# Arduino_NANO_DRAM_Tester.net
KiCad netlist of a schematic drawn in EAGLE
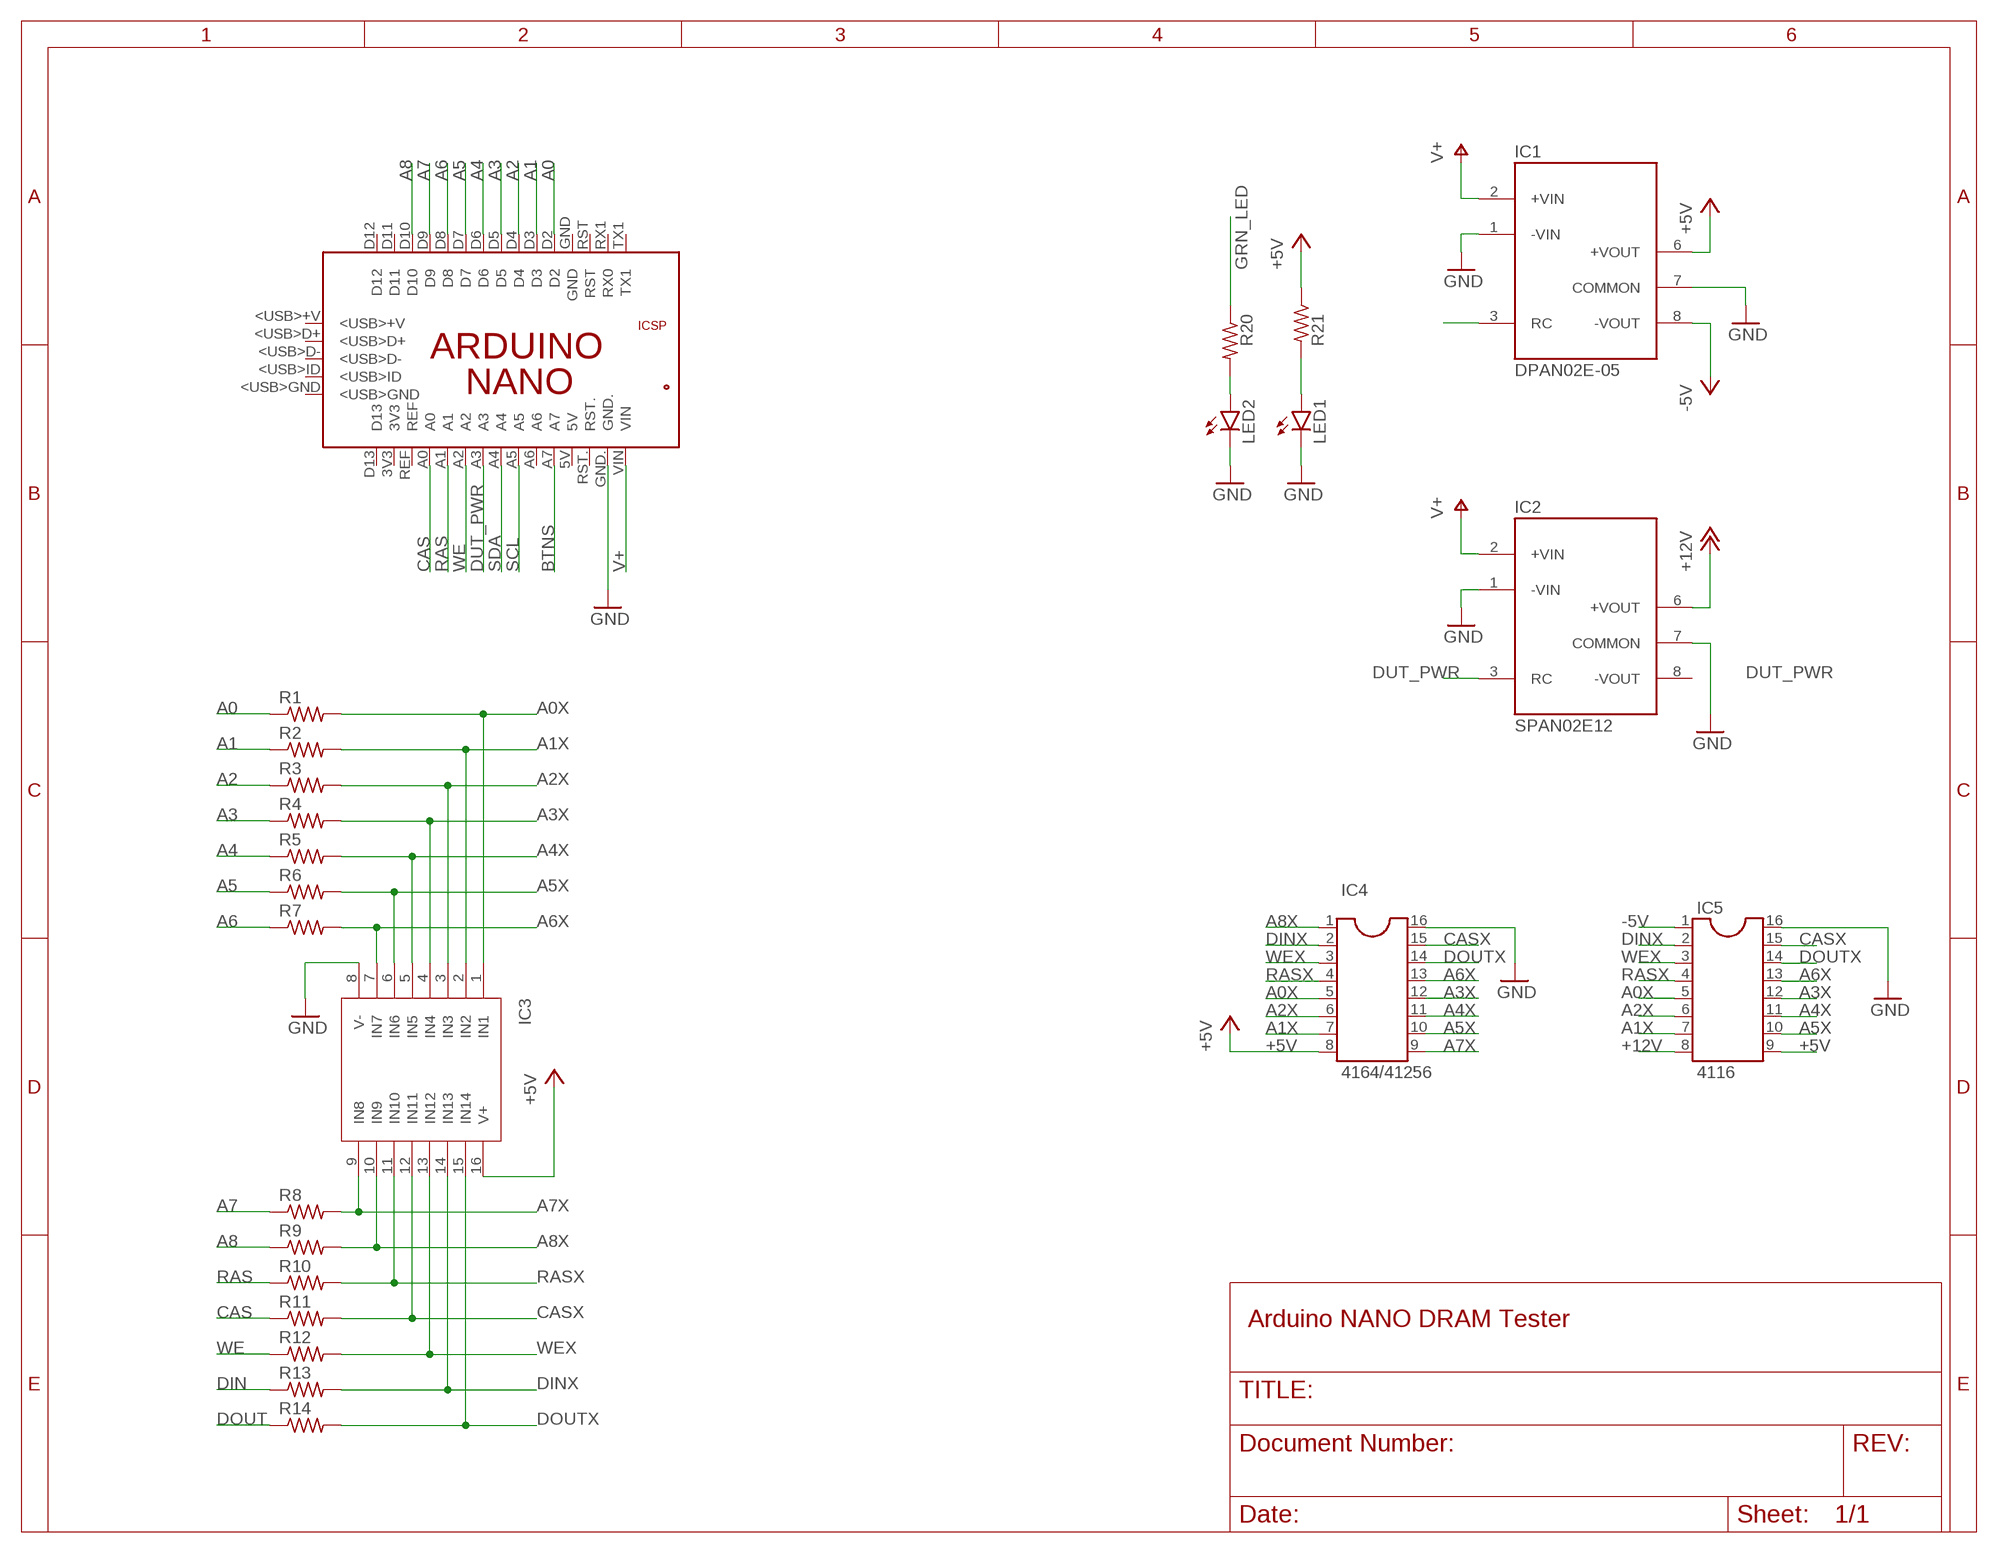
[diagram p0: schematic, sheet 1]

(export (version "E")
  (design (tool "Eeschema 10.0.6"))
  (components
    (comp (ref "IC1")
      (value "DPAN02E-05")
      (footprint "eagle-import:SIP7")
      (libsource (lib "eagle-import") (part "DPAN02"))
    )
    (comp (ref "IC2")
      (value "SPAN02E12")
      (footprint "eagle-import:SIP7")
      (libsource (lib "eagle-import") (part "DPAN02"))
    )
    (comp (ref "IC3")
      (value "SP720")
      (footprint "eagle-import:DIL16")
      (libsource (lib "eagle-import") (part "SP720"))
    )
    (comp (ref "IC4")
      (value "4164/41256")
      (footprint "eagle-import:DIL16")
      (libsource (lib "eagle-import") (part "DIL16"))
    )
    (comp (ref "IC5")
      (value "4116")
      (footprint "eagle-import:SOCKET-16")
      (libsource (lib "eagle-import") (part "DIL16S"))
    )
    (comp (ref "LED1")
      (value "LED5MM")
      (footprint "eagle-import:LED5MM")
      (libsource (lib "eagle-import") (part "LED5MM"))
    )
    (comp (ref "LED2")
      (value "LED5MM")
      (footprint "eagle-import:LED5MM")
      (libsource (lib "eagle-import") (part "LED5MM"))
    )
    (comp (ref "PCB1")
      (value "ARDUINO_NANO")
      (footprint "eagle-import:ARDUINO_NANO")
      (libsource (lib "eagle-import") (part "ARDUINO_NANO"))
    )
    (comp (ref "R1")
      (value "R-US_V235/17")
      (footprint "eagle-import:V235_17")
      (libsource (lib "eagle-import") (part "R-US_V235/17"))
    )
    (comp (ref "R2")
      (value "R-US_V235/17")
      (footprint "eagle-import:V235_17")
      (libsource (lib "eagle-import") (part "R-US_V235/17"))
    )
    (comp (ref "R3")
      (value "R-US_V235/17")
      (footprint "eagle-import:V235_17")
      (libsource (lib "eagle-import") (part "R-US_V235/17"))
    )
    (comp (ref "R4")
      (value "R-US_V235/17")
      (footprint "eagle-import:V235_17")
      (libsource (lib "eagle-import") (part "R-US_V235/17"))
    )
    (comp (ref "R5")
      (value "R-US_V235/17")
      (footprint "eagle-import:V235_17")
      (libsource (lib "eagle-import") (part "R-US_V235/17"))
    )
    (comp (ref "R6")
      (value "R-US_V235/17")
      (footprint "eagle-import:V235_17")
      (libsource (lib "eagle-import") (part "R-US_V235/17"))
    )
    (comp (ref "R7")
      (value "R-US_V235/17")
      (footprint "eagle-import:V235_17")
      (libsource (lib "eagle-import") (part "R-US_V235/17"))
    )
    (comp (ref "R8")
      (value "R-US_V235/17")
      (footprint "eagle-import:V235_17")
      (libsource (lib "eagle-import") (part "R-US_V235/17"))
    )
    (comp (ref "R9")
      (value "R-US_V235/17")
      (footprint "eagle-import:V235_17")
      (libsource (lib "eagle-import") (part "R-US_V235/17"))
    )
    (comp (ref "R10")
      (value "R-US_V235/17")
      (footprint "eagle-import:V235_17")
      (libsource (lib "eagle-import") (part "R-US_V235/17"))
    )
    (comp (ref "R11")
      (value "R-US_V235/17")
      (footprint "eagle-import:V235_17")
      (libsource (lib "eagle-import") (part "R-US_V235/17"))
    )
    (comp (ref "R12")
      (value "R-US_V235/17")
      (footprint "eagle-import:V235_17")
      (libsource (lib "eagle-import") (part "R-US_V235/17"))
    )
    (comp (ref "R13")
      (value "R-US_V235/17")
      (footprint "eagle-import:V235_17")
      (libsource (lib "eagle-import") (part "R-US_V235/17"))
    )
    (comp (ref "R14")
      (value "R-US_V235/17")
      (footprint "eagle-import:V235_17")
      (libsource (lib "eagle-import") (part "R-US_V235/17"))
    )
    (comp (ref "R20")
      (value "R-US_0309/10")
      (footprint "eagle-import:0309_10")
      (libsource (lib "eagle-import") (part "resistor_348_R-US_0309/10"))
    )
    (comp (ref "R21")
      (value "R-US_0309/10")
      (footprint "eagle-import:0309_10")
      (libsource (lib "eagle-import") (part "resistor_348_R-US_0309/10"))
    )
  )
  (nets
    (net (code "1") (name "+5V") (class "Default")
      (node (ref "IC1") (pin "6") (pinfunction "+VOUT_6") (pintype "passive"))
      (node (ref "IC3") (pin "16") (pinfunction "V+_16") (pintype "input"))
      (node (ref "IC4") (pin "8") (pinfunction "8_8") (pintype "passive"))
      (node (ref "IC5") (pin "9") (pinfunction "9_9") (pintype "passive"))
      (node (ref "R21") (pin "1") (pinfunction "1_1") (pintype "passive"))
    )
    (net (code "2") (name "+12V") (class "Default")
      (node (ref "IC2") (pin "6") (pinfunction "+VOUT_6") (pintype "passive"))
      (node (ref "IC5") (pin "8") (pinfunction "8_8") (pintype "passive"))
    )
    (net (code "3") (name "-5V") (class "Default")
      (node (ref "IC1") (pin "8") (pinfunction "-VOUT_8") (pintype "passive"))
      (node (ref "IC5") (pin "1") (pinfunction "1_1") (pintype "passive"))
    )
    (net (code "4") (name "/A0") (class "Default")
      (node (ref "PCB1") (pin "D2") (pinfunction "D2_D2") (pintype "bidirectional"))
      (node (ref "R1") (pin "1") (pinfunction "1_1") (pintype "passive"))
    )
    (net (code "5") (name "/A0X") (class "Default")
      (node (ref "IC3") (pin "1") (pinfunction "IN1_1") (pintype "input"))
      (node (ref "IC4") (pin "5") (pinfunction "5_5") (pintype "passive"))
      (node (ref "IC5") (pin "5") (pinfunction "5_5") (pintype "passive"))
      (node (ref "R1") (pin "2") (pinfunction "2_2") (pintype "passive"))
    )
    (net (code "6") (name "/A1") (class "Default")
      (node (ref "PCB1") (pin "D3") (pinfunction "D3_D3") (pintype "bidirectional"))
      (node (ref "R2") (pin "1") (pinfunction "1_1") (pintype "passive"))
    )
    (net (code "7") (name "/A1X") (class "Default")
      (node (ref "IC3") (pin "2") (pinfunction "IN2_2") (pintype "input"))
      (node (ref "IC4") (pin "7") (pinfunction "7_7") (pintype "passive"))
      (node (ref "IC5") (pin "7") (pinfunction "7_7") (pintype "passive"))
      (node (ref "R2") (pin "2") (pinfunction "2_2") (pintype "passive"))
    )
    (net (code "8") (name "/A2") (class "Default")
      (node (ref "PCB1") (pin "D4") (pinfunction "D4_D4") (pintype "bidirectional"))
      (node (ref "R3") (pin "1") (pinfunction "1_1") (pintype "passive"))
    )
    (net (code "9") (name "/A2X") (class "Default")
      (node (ref "IC3") (pin "3") (pinfunction "IN3_3") (pintype "input"))
      (node (ref "IC4") (pin "6") (pinfunction "6_6") (pintype "passive"))
      (node (ref "IC5") (pin "6") (pinfunction "6_6") (pintype "passive"))
      (node (ref "R3") (pin "2") (pinfunction "2_2") (pintype "passive"))
    )
    (net (code "10") (name "/A3") (class "Default")
      (node (ref "PCB1") (pin "D5") (pinfunction "D5_D5") (pintype "bidirectional"))
      (node (ref "R4") (pin "1") (pinfunction "1_1") (pintype "passive"))
    )
    (net (code "11") (name "/A3X") (class "Default")
      (node (ref "IC3") (pin "4") (pinfunction "IN4_4") (pintype "input"))
      (node (ref "IC4") (pin "12") (pinfunction "12_12") (pintype "passive"))
      (node (ref "IC5") (pin "12") (pinfunction "12_12") (pintype "passive"))
      (node (ref "R4") (pin "2") (pinfunction "2_2") (pintype "passive"))
    )
    (net (code "12") (name "/A4") (class "Default")
      (node (ref "PCB1") (pin "D6") (pinfunction "D6_D6") (pintype "bidirectional"))
      (node (ref "R5") (pin "1") (pinfunction "1_1") (pintype "passive"))
    )
    (net (code "13") (name "/A4X") (class "Default")
      (node (ref "IC3") (pin "5") (pinfunction "IN5_5") (pintype "input"))
      (node (ref "IC4") (pin "11") (pinfunction "11_11") (pintype "passive"))
      (node (ref "IC5") (pin "11") (pinfunction "11_11") (pintype "passive"))
      (node (ref "R5") (pin "2") (pinfunction "2_2") (pintype "passive"))
    )
    (net (code "14") (name "/A5") (class "Default")
      (node (ref "PCB1") (pin "D7") (pinfunction "D7_D7") (pintype "bidirectional"))
      (node (ref "R6") (pin "1") (pinfunction "1_1") (pintype "passive"))
    )
    (net (code "15") (name "/A5X") (class "Default")
      (node (ref "IC3") (pin "6") (pinfunction "IN6_6") (pintype "input"))
      (node (ref "IC4") (pin "10") (pinfunction "10_10") (pintype "passive"))
      (node (ref "IC5") (pin "10") (pinfunction "10_10") (pintype "passive"))
      (node (ref "R6") (pin "2") (pinfunction "2_2") (pintype "passive"))
    )
    (net (code "16") (name "/A6") (class "Default")
      (node (ref "PCB1") (pin "D8") (pinfunction "D8_D8") (pintype "bidirectional"))
      (node (ref "R7") (pin "1") (pinfunction "1_1") (pintype "passive"))
    )
    (net (code "17") (name "/A6X") (class "Default")
      (node (ref "IC3") (pin "7") (pinfunction "IN7_7") (pintype "input"))
      (node (ref "IC4") (pin "13") (pinfunction "13_13") (pintype "passive"))
      (node (ref "IC5") (pin "13") (pinfunction "13_13") (pintype "passive"))
      (node (ref "R7") (pin "2") (pinfunction "2_2") (pintype "passive"))
    )
    (net (code "18") (name "/A7") (class "Default")
      (node (ref "PCB1") (pin "D9") (pinfunction "D9_D9") (pintype "bidirectional"))
      (node (ref "R8") (pin "1") (pinfunction "1_1") (pintype "passive"))
    )
    (net (code "19") (name "/A7X") (class "Default")
      (node (ref "IC3") (pin "9") (pinfunction "IN8_9") (pintype "input"))
      (node (ref "IC4") (pin "9") (pinfunction "9_9") (pintype "passive"))
      (node (ref "R8") (pin "2") (pinfunction "2_2") (pintype "passive"))
    )
    (net (code "20") (name "/A8") (class "Default")
      (node (ref "PCB1") (pin "D10") (pinfunction "D10_D10") (pintype "bidirectional"))
      (node (ref "R9") (pin "1") (pinfunction "1_1") (pintype "passive"))
    )
    (net (code "21") (name "/A8X") (class "Default")
      (node (ref "IC3") (pin "10") (pinfunction "IN9_10") (pintype "input"))
      (node (ref "IC4") (pin "1") (pinfunction "1_1") (pintype "passive"))
      (node (ref "R9") (pin "2") (pinfunction "2_2") (pintype "passive"))
    )
    (net (code "22") (name "/BTNS") (class "Default")
      (node (ref "PCB1") (pin "A7") (pinfunction "A7_A7") (pintype "bidirectional"))
    )
    (net (code "23") (name "/CAS") (class "Default")
      (node (ref "PCB1") (pin "A0") (pinfunction "A0_A0") (pintype "bidirectional"))
      (node (ref "R11") (pin "1") (pinfunction "1_1") (pintype "passive"))
    )
    (net (code "24") (name "/CASX") (class "Default")
      (node (ref "IC3") (pin "12") (pinfunction "IN11_12") (pintype "input"))
      (node (ref "IC4") (pin "15") (pinfunction "15_15") (pintype "passive"))
      (node (ref "IC5") (pin "15") (pinfunction "15_15") (pintype "passive"))
      (node (ref "R11") (pin "2") (pinfunction "2_2") (pintype "passive"))
    )
    (net (code "25") (name "/DIN") (class "Default")
      (node (ref "R13") (pin "1") (pinfunction "1_1") (pintype "passive"))
    )
    (net (code "26") (name "/DINX") (class "Default")
      (node (ref "IC3") (pin "14") (pinfunction "IN13_14") (pintype "input"))
      (node (ref "IC4") (pin "2") (pinfunction "2_2") (pintype "passive"))
      (node (ref "IC5") (pin "2") (pinfunction "2_2") (pintype "passive"))
      (node (ref "R13") (pin "2") (pinfunction "2_2") (pintype "passive"))
    )
    (net (code "27") (name "/DOUT") (class "Default")
      (node (ref "R14") (pin "1") (pinfunction "1_1") (pintype "passive"))
    )
    (net (code "28") (name "/DOUTX") (class "Default")
      (node (ref "IC3") (pin "15") (pinfunction "IN14_15") (pintype "input"))
      (node (ref "IC4") (pin "14") (pinfunction "14_14") (pintype "passive"))
      (node (ref "IC5") (pin "14") (pinfunction "14_14") (pintype "passive"))
      (node (ref "R14") (pin "2") (pinfunction "2_2") (pintype "passive"))
    )
    (net (code "29") (name "/DUT_PWR") (class "Default")
      (node (ref "IC1") (pin "3") (pinfunction "RC_3") (pintype "input"))
      (node (ref "IC2") (pin "3") (pinfunction "RC_3") (pintype "input"))
      (node (ref "PCB1") (pin "A3") (pinfunction "A3_A3") (pintype "bidirectional"))
    )
    (net (code "30") (name "/GRN_LED") (class "Default")
      (node (ref "R20") (pin "1") (pinfunction "1_1") (pintype "passive"))
    )
    (net (code "31") (name "/RAS") (class "Default")
      (node (ref "PCB1") (pin "A1") (pinfunction "A1_A1") (pintype "bidirectional"))
      (node (ref "R10") (pin "1") (pinfunction "1_1") (pintype "passive"))
    )
    (net (code "32") (name "/RASX") (class "Default")
      (node (ref "IC3") (pin "11") (pinfunction "IN10_11") (pintype "input"))
      (node (ref "IC4") (pin "4") (pinfunction "4_4") (pintype "passive"))
      (node (ref "IC5") (pin "4") (pinfunction "4_4") (pintype "passive"))
      (node (ref "R10") (pin "2") (pinfunction "2_2") (pintype "passive"))
    )
    (net (code "33") (name "/SCL") (class "Default")
      (node (ref "PCB1") (pin "A5") (pinfunction "A5_A5") (pintype "bidirectional"))
    )
    (net (code "34") (name "/SDA") (class "Default")
      (node (ref "PCB1") (pin "A4") (pinfunction "A4_A4") (pintype "bidirectional"))
    )
    (net (code "35") (name "/WE") (class "Default")
      (node (ref "PCB1") (pin "A2") (pinfunction "A2_A2") (pintype "bidirectional"))
      (node (ref "R12") (pin "1") (pinfunction "1_1") (pintype "passive"))
    )
    (net (code "36") (name "/WEX") (class "Default")
      (node (ref "IC3") (pin "13") (pinfunction "IN12_13") (pintype "input"))
      (node (ref "IC4") (pin "3") (pinfunction "3_3") (pintype "passive"))
      (node (ref "IC5") (pin "3") (pinfunction "3_3") (pintype "passive"))
      (node (ref "R12") (pin "2") (pinfunction "2_2") (pintype "passive"))
    )
    (net (code "37") (name "GND") (class "Default")
      (node (ref "IC1") (pin "1") (pinfunction "-VIN_1") (pintype "input"))
      (node (ref "IC1") (pin "7") (pinfunction "COMMON_7") (pintype "passive"))
      (node (ref "IC2") (pin "1") (pinfunction "-VIN_1") (pintype "input"))
      (node (ref "IC2") (pin "7") (pinfunction "COMMON_7") (pintype "passive"))
      (node (ref "IC3") (pin "8") (pinfunction "V-_8") (pintype "input"))
      (node (ref "IC4") (pin "16") (pinfunction "16_16") (pintype "passive"))
      (node (ref "IC5") (pin "16") (pinfunction "16_16") (pintype "passive"))
      (node (ref "LED1") (pin "K") (pinfunction "C_K") (pintype "passive"))
      (node (ref "LED2") (pin "K") (pinfunction "C_K") (pintype "passive"))
      (node (ref "PCB1") (pin "GND.") (pinfunction "GND._GND.") (pintype "bidirectional"))
    )
    (net (code "38") (name "Net-(LED1-PadA)") (class "Default")
      (node (ref "LED1") (pin "A") (pinfunction "A_A") (pintype "passive"))
      (node (ref "R21") (pin "2") (pinfunction "2_2") (pintype "passive"))
    )
    (net (code "39") (name "Net-(LED2-PadA)") (class "Default")
      (node (ref "LED2") (pin "A") (pinfunction "A_A") (pintype "passive"))
      (node (ref "R20") (pin "2") (pinfunction "2_2") (pintype "passive"))
    )
    (net (code "40") (name "V+") (class "Default")
      (node (ref "IC1") (pin "2") (pinfunction "+VIN_2") (pintype "input"))
      (node (ref "IC2") (pin "2") (pinfunction "+VIN_2") (pintype "input"))
      (node (ref "PCB1") (pin "VIN") (pinfunction "VIN_VIN") (pintype "bidirectional"))
    )
    (net (code "41") (name "unconnected-(IC2--VOUT-Pad8)") (class "Default")
      (node (ref "IC2") (pin "8") (pinfunction "-VOUT_8") (pintype "passive"))
    )
    (net (code "42") (name "unconnected-(PCB1-Pad3V3)") (class "Default")
      (node (ref "PCB1") (pin "3V3") (pinfunction "3V3_3V3") (pintype "bidirectional"))
    )
    (net (code "43") (name "unconnected-(PCB1-Pad5V)") (class "Default")
      (node (ref "PCB1") (pin "5V") (pinfunction "5V_5V") (pintype "bidirectional"))
    )
    (net (code "44") (name "unconnected-(PCB1-Pad5V.)") (class "Default")
      (node (ref "PCB1") (pin "5V.") (pinfunction "5V._5V.") (pintype "bidirectional"))
    )
    (net (code "45") (name "unconnected-(PCB1-Pad<USB>+V)") (class "Default")
      (node (ref "PCB1") (pin "<USB>+V") (pinfunction "<USB>+V_<USB>+V") (pintype "bidirectional"))
    )
    (net (code "46") (name "unconnected-(PCB1-Pad<USB>D+)") (class "Default")
      (node (ref "PCB1") (pin "<USB>D+") (pinfunction "<USB>D+_<USB>D+") (pintype "bidirectional"))
    )
    (net (code "47") (name "unconnected-(PCB1-Pad<USB>D-)") (class "Default")
      (node (ref "PCB1") (pin "<USB>D-") (pinfunction "<USB>D-_<USB>D-") (pintype "bidirectional"))
    )
    (net (code "48") (name "unconnected-(PCB1-Pad<USB>GND)") (class "Default")
      (node (ref "PCB1") (pin "<USB>GND") (pinfunction "<USB>GND_<USB>GND") (pintype "bidirectional"))
    )
    (net (code "49") (name "unconnected-(PCB1-Pad<USB>ID)") (class "Default")
      (node (ref "PCB1") (pin "<USB>ID") (pinfunction "<USB>ID_<USB>ID") (pintype "bidirectional"))
    )
    (net (code "50") (name "unconnected-(PCB1-PadA6)") (class "Default")
      (node (ref "PCB1") (pin "A6") (pinfunction "A6_A6") (pintype "bidirectional"))
    )
    (net (code "51") (name "unconnected-(PCB1-PadD11)") (class "Default")
      (node (ref "PCB1") (pin "D11") (pinfunction "D11_D11") (pintype "bidirectional"))
    )
    (net (code "52") (name "unconnected-(PCB1-PadD12)") (class "Default")
      (node (ref "PCB1") (pin "D12") (pinfunction "D12_D12") (pintype "bidirectional"))
    )
    (net (code "53") (name "unconnected-(PCB1-PadD13)") (class "Default")
      (node (ref "PCB1") (pin "D13") (pinfunction "D13_D13") (pintype "bidirectional"))
    )
    (net (code "54") (name "unconnected-(PCB1-PadGND)") (class "Default")
      (node (ref "PCB1") (pin "GND") (pinfunction "GND_GND") (pintype "bidirectional"))
    )
    (net (code "55") (name "unconnected-(PCB1-PadGND_)") (class "Default")
      (node (ref "PCB1") (pin "GND_") (pinfunction "GND__GND_") (pintype "bidirectional"))
    )
    (net (code "56") (name "unconnected-(PCB1-PadMISO)") (class "Default")
      (node (ref "PCB1") (pin "MISO") (pinfunction "MISO_MISO") (pintype "bidirectional"))
    )
    (net (code "57") (name "unconnected-(PCB1-PadMOSI)") (class "Default")
      (node (ref "PCB1") (pin "MOSI") (pinfunction "MOSI_MOSI") (pintype "bidirectional"))
    )
    (net (code "58") (name "unconnected-(PCB1-PadREF)") (class "Default")
      (node (ref "PCB1") (pin "REF") (pinfunction "REF_REF") (pintype "bidirectional"))
    )
    (net (code "59") (name "unconnected-(PCB1-PadRESET..)") (class "Default")
      (node (ref "PCB1") (pin "RESET..") (pinfunction "RESET.._RESET..") (pintype "bidirectional"))
    )
    (net (code "60") (name "unconnected-(PCB1-PadRST)") (class "Default")
      (node (ref "PCB1") (pin "RST") (pinfunction "RST_RST") (pintype "bidirectional"))
    )
    (net (code "61") (name "unconnected-(PCB1-PadRST.)") (class "Default")
      (node (ref "PCB1") (pin "RST.") (pinfunction "RST._RST.") (pintype "bidirectional"))
    )
    (net (code "62") (name "unconnected-(PCB1-PadSCK)") (class "Default")
      (node (ref "PCB1") (pin "SCK") (pinfunction "SCK_SCK") (pintype "bidirectional"))
    )
    (net (code "63") (name "unconnected-(PCB1-PadTX1)") (class "Default")
      (node (ref "PCB1") (pin "TX1") (pinfunction "TX1_TX1") (pintype "bidirectional"))
    )
    (net (code "64") (name "unconnected-(PCB1-RX0-PadRX1)") (class "Default")
      (node (ref "PCB1") (pin "RX1") (pinfunction "RX0_RX1") (pintype "bidirectional"))
    )
  )
)
